# BiphasicBoardv2.net
KiCad netlist of a schematic drawn in EAGLE
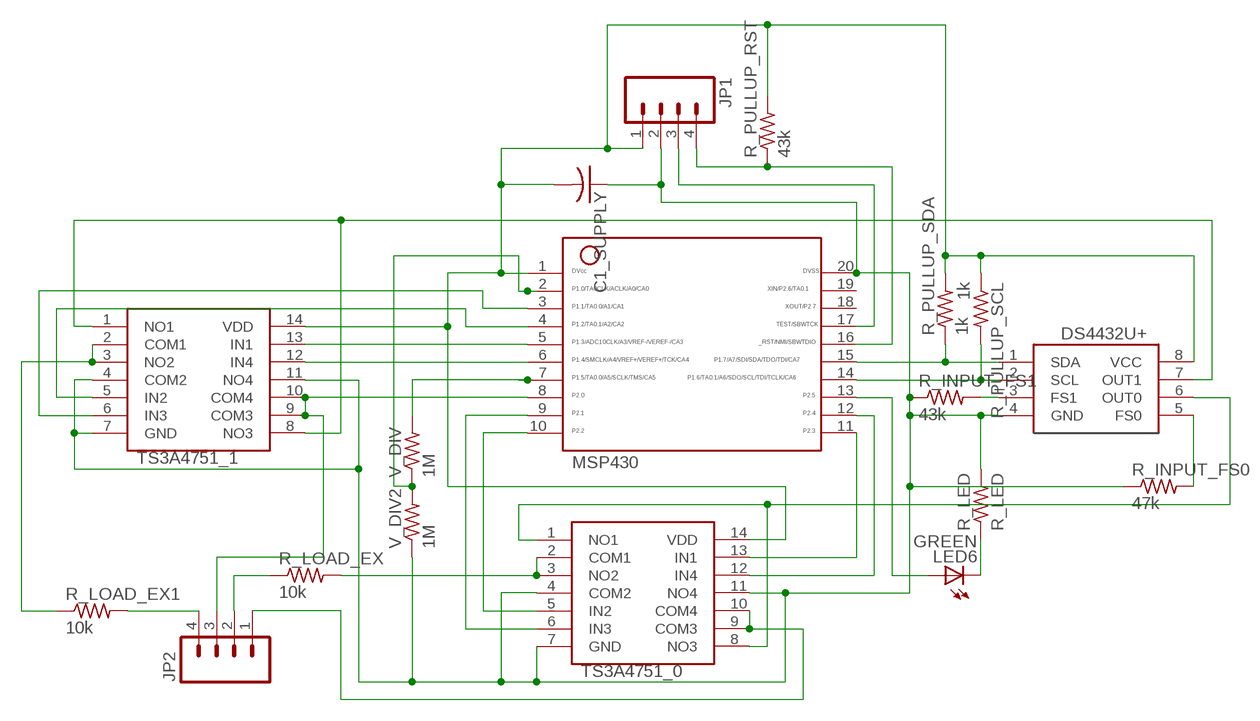
[diagram p0: schematic, sheet 1]

(export (version "E")
  (design (tool "Eeschema 10.0.6"))
  (components
    (comp (ref "C1_SUPPLY")
      (value "C-USC0603")
      (footprint "eagle-import:C0603")
      (libsource (lib "eagle-import") (part "C-USC0603"))
    )
    (comp (ref "DS4432U+")
      (value "DS4432U+")
      (footprint "eagle-import:8_PIN")
      (libsource (lib "eagle-import") (part "DS4432U+"))
    )
    (comp (ref "JP1")
      (value "M041.27MM")
      (footprint "eagle-import:1X04-1.27MM")
      (libsource (lib "eagle-import") (part "M041.27MM"))
    )
    (comp (ref "JP2")
      (value "M041.27MM")
      (footprint "eagle-import:1X04-1.27MM")
      (libsource (lib "eagle-import") (part "M041.27MM"))
    )
    (comp (ref "LED6")
      (value "GREEN")
      (footprint "eagle-import:LED-1206")
      (libsource (lib "eagle-import") (part "LED1206"))
    )
    (comp (ref "MSP430")
      (value "MSP430")
      (footprint "eagle-import:20_PIN")
      (libsource (lib "eagle-import") (part "MSP430"))
    )
    (comp (ref "R_INPUT_FS0")
      (value "47k")
      (footprint "eagle-import:R0603")
      (libsource (lib "eagle-import") (part "R-US_R0603"))
    )
    (comp (ref "R_INPUT_FS1")
      (value "43k")
      (footprint "eagle-import:R0603")
      (libsource (lib "eagle-import") (part "R-US_R0603"))
    )
    (comp (ref "R_LED")
      (value "R_LED")
      (footprint "eagle-import:R0603")
      (libsource (lib "eagle-import") (part "R-US_R0603"))
    )
    (comp (ref "R_LOAD_EX")
      (value "10k")
      (footprint "eagle-import:R0603")
      (libsource (lib "eagle-import") (part "R-US_R0603"))
    )
    (comp (ref "R_LOAD_EX1")
      (value "10k")
      (footprint "eagle-import:R0603")
      (libsource (lib "eagle-import") (part "R-US_R0603"))
    )
    (comp (ref "R_PULLUP_RST")
      (value "43k")
      (footprint "eagle-import:R0603")
      (libsource (lib "eagle-import") (part "R-US_R0603"))
    )
    (comp (ref "R_PULLUP_SCL")
      (value "1k")
      (footprint "eagle-import:R0603")
      (libsource (lib "eagle-import") (part "R-US_R0603"))
    )
    (comp (ref "R_PULLUP_SDA")
      (value "1k")
      (footprint "eagle-import:R0603")
      (libsource (lib "eagle-import") (part "R-US_R0603"))
    )
    (comp (ref "TS3A4751_0")
      (value "TS3A4751")
      (footprint "eagle-import:14_PIN")
      (libsource (lib "eagle-import") (part "TS3A4751"))
    )
    (comp (ref "TS3A4751_1")
      (value "TS3A4751")
      (footprint "eagle-import:14_PIN")
      (libsource (lib "eagle-import") (part "TS3A4751"))
    )
    (comp (ref "V_DIV")
      (value "1M")
      (footprint "eagle-import:R0603")
      (libsource (lib "eagle-import") (part "R-US_R0603"))
    )
    (comp (ref "V_DIV2")
      (value "1M")
      (footprint "eagle-import:R0603")
      (libsource (lib "eagle-import") (part "R-US_R0603"))
    )
  )
  (nets
    (net (code "1") (name "Net-(DS4432U+-FS0)") (class "Default")
      (node (ref "DS4432U+") (pin "5") (pinfunction "FS0_5") (pintype "bidirectional"))
      (node (ref "R_INPUT_FS0") (pin "2") (pinfunction "2_2") (pintype "passive"))
    )
    (net (code "2") (name "Net-(DS4432U+-FS1)") (class "Default")
      (node (ref "DS4432U+") (pin "3") (pinfunction "FS1_3") (pintype "bidirectional"))
      (node (ref "R_INPUT_FS1") (pin "2") (pinfunction "2_2") (pintype "passive"))
    )
    (net (code "3") (name "Net-(DS4432U+-GND)") (class "Default")
      (node (ref "C1_SUPPLY") (pin "1") (pinfunction "1_1") (pintype "passive"))
      (node (ref "DS4432U+") (pin "4") (pinfunction "GND_4") (pintype "bidirectional"))
      (node (ref "JP1") (pin "2") (pinfunction "2_2") (pintype "passive"))
      (node (ref "MSP430") (pin "20") (pinfunction "20_20") (pintype "bidirectional"))
      (node (ref "R_INPUT_FS0") (pin "1") (pinfunction "1_1") (pintype "passive"))
      (node (ref "R_INPUT_FS1") (pin "1") (pinfunction "1_1") (pintype "passive"))
      (node (ref "R_LED") (pin "2") (pinfunction "2_2") (pintype "passive"))
      (node (ref "TS3A4751_0") (pin "11") (pinfunction "NO4_11") (pintype "bidirectional"))
      (node (ref "TS3A4751_0") (pin "4") (pinfunction "COM2_4") (pintype "bidirectional"))
      (node (ref "TS3A4751_0") (pin "7") (pinfunction "GND_7") (pintype "bidirectional"))
      (node (ref "TS3A4751_1") (pin "11") (pinfunction "NO4_11") (pintype "bidirectional"))
      (node (ref "TS3A4751_1") (pin "4") (pinfunction "COM2_4") (pintype "bidirectional"))
      (node (ref "TS3A4751_1") (pin "7") (pinfunction "GND_7") (pintype "bidirectional"))
      (node (ref "V_DIV2") (pin "1") (pinfunction "1_1") (pintype "passive"))
    )
    (net (code "4") (name "Net-(DS4432U+-OUT0)") (class "Default")
      (node (ref "DS4432U+") (pin "6") (pinfunction "OUT0_6") (pintype "bidirectional"))
      (node (ref "TS3A4751_0") (pin "1") (pinfunction "NO1_1") (pintype "bidirectional"))
      (node (ref "TS3A4751_0") (pin "8") (pinfunction "NO3_8") (pintype "bidirectional"))
    )
    (net (code "5") (name "Net-(DS4432U+-OUT1)") (class "Default")
      (node (ref "DS4432U+") (pin "7") (pinfunction "OUT1_7") (pintype "bidirectional"))
      (node (ref "TS3A4751_1") (pin "1") (pinfunction "NO1_1") (pintype "bidirectional"))
      (node (ref "TS3A4751_1") (pin "8") (pinfunction "NO3_8") (pintype "bidirectional"))
    )
    (net (code "6") (name "Net-(DS4432U+-SCL)") (class "Default")
      (node (ref "DS4432U+") (pin "2") (pinfunction "SCL_2") (pintype "bidirectional"))
      (node (ref "MSP430") (pin "14") (pinfunction "14_14") (pintype "bidirectional"))
      (node (ref "R_PULLUP_SCL") (pin "2") (pinfunction "2_2") (pintype "passive"))
    )
    (net (code "7") (name "Net-(DS4432U+-SDA)") (class "Default")
      (node (ref "DS4432U+") (pin "1") (pinfunction "SDA_1") (pintype "bidirectional"))
      (node (ref "MSP430") (pin "15") (pinfunction "15_15") (pintype "bidirectional"))
      (node (ref "R_PULLUP_SDA") (pin "1") (pinfunction "1_1") (pintype "passive"))
    )
    (net (code "8") (name "Net-(DS4432U+-VCC)") (class "Default")
      (node (ref "C1_SUPPLY") (pin "2") (pinfunction "2_2") (pintype "passive"))
      (node (ref "DS4432U+") (pin "8") (pinfunction "VCC_8") (pintype "bidirectional"))
      (node (ref "JP1") (pin "1") (pinfunction "1_1") (pintype "passive"))
      (node (ref "MSP430") (pin "1") (pinfunction "1_1") (pintype "bidirectional"))
      (node (ref "R_PULLUP_RST") (pin "2") (pinfunction "2_2") (pintype "passive"))
      (node (ref "R_PULLUP_SCL") (pin "1") (pinfunction "1_1") (pintype "passive"))
      (node (ref "R_PULLUP_SDA") (pin "2") (pinfunction "2_2") (pintype "passive"))
      (node (ref "TS3A4751_0") (pin "14") (pinfunction "VDD_14") (pintype "bidirectional"))
      (node (ref "TS3A4751_1") (pin "14") (pinfunction "VDD_14") (pintype "bidirectional"))
    )
    (net (code "9") (name "Net-(JP1-Pad3)") (class "Default")
      (node (ref "JP1") (pin "3") (pinfunction "3_3") (pintype "passive"))
      (node (ref "MSP430") (pin "17") (pinfunction "17_17") (pintype "bidirectional"))
    )
    (net (code "10") (name "Net-(JP1-Pad4)") (class "Default")
      (node (ref "JP1") (pin "4") (pinfunction "4_4") (pintype "passive"))
      (node (ref "MSP430") (pin "16") (pinfunction "16_16") (pintype "bidirectional"))
      (node (ref "R_PULLUP_RST") (pin "1") (pinfunction "1_1") (pintype "passive"))
    )
    (net (code "11") (name "Net-(JP2-Pad2)") (class "Default")
      (node (ref "JP2") (pin "2") (pinfunction "2_2") (pintype "passive"))
      (node (ref "R_LOAD_EX") (pin "1") (pinfunction "1_1") (pintype "passive"))
    )
    (net (code "12") (name "Net-(JP2-Pad4)") (class "Default")
      (node (ref "JP2") (pin "4") (pinfunction "4_4") (pintype "passive"))
      (node (ref "R_LOAD_EX1") (pin "2") (pinfunction "2_2") (pintype "passive"))
    )
    (net (code "13") (name "Net-(LED6-PadA)") (class "Default")
      (node (ref "LED6") (pin "A") (pinfunction "A_A") (pintype "passive"))
      (node (ref "MSP430") (pin "13") (pinfunction "13_13") (pintype "bidirectional"))
    )
    (net (code "14") (name "Net-(LED6-PadC)") (class "Default")
      (node (ref "LED6") (pin "C") (pinfunction "C_C") (pintype "passive"))
      (node (ref "R_LED") (pin "1") (pinfunction "1_1") (pintype "passive"))
    )
    (net (code "15") (name "Net-(MSP430-Pad2)") (class "Default")
      (node (ref "MSP430") (pin "2") (pinfunction "2_2") (pintype "bidirectional"))
      (node (ref "V_DIV") (pin "1") (pinfunction "1_1") (pintype "passive"))
      (node (ref "V_DIV2") (pin "2") (pinfunction "2_2") (pintype "passive"))
    )
    (net (code "16") (name "Net-(MSP430-Pad7)") (class "Default")
      (node (ref "MSP430") (pin "7") (pinfunction "7_7") (pintype "bidirectional"))
      (node (ref "V_DIV") (pin "2") (pinfunction "2_2") (pintype "passive"))
    )
    (net (code "17") (name "Net-(TS3A4751_0-COM1)") (class "Default")
      (node (ref "R_LOAD_EX") (pin "2") (pinfunction "2_2") (pintype "passive"))
      (node (ref "TS3A4751_0") (pin "2") (pinfunction "COM1_2") (pintype "bidirectional"))
      (node (ref "TS3A4751_0") (pin "3") (pinfunction "NO2_3") (pintype "bidirectional"))
    )
    (net (code "18") (name "Net-(TS3A4751_0-COM3)") (class "Default")
      (node (ref "JP2") (pin "1") (pinfunction "1_1") (pintype "passive"))
      (node (ref "TS3A4751_0") (pin "10") (pinfunction "COM4_10") (pintype "bidirectional"))
      (node (ref "TS3A4751_0") (pin "9") (pinfunction "COM3_9") (pintype "bidirectional"))
    )
    (net (code "19") (name "Net-(TS3A4751_0-IN1)") (class "Default")
      (node (ref "MSP430") (pin "11") (pinfunction "11_11") (pintype "bidirectional"))
      (node (ref "TS3A4751_0") (pin "13") (pinfunction "IN1_13") (pintype "bidirectional"))
    )
    (net (code "20") (name "Net-(TS3A4751_0-IN2)") (class "Default")
      (node (ref "MSP430") (pin "10") (pinfunction "10_10") (pintype "bidirectional"))
      (node (ref "TS3A4751_0") (pin "5") (pinfunction "IN2_5") (pintype "bidirectional"))
    )
    (net (code "21") (name "Net-(TS3A4751_0-IN3)") (class "Default")
      (node (ref "MSP430") (pin "9") (pinfunction "9_9") (pintype "bidirectional"))
      (node (ref "TS3A4751_0") (pin "6") (pinfunction "IN3_6") (pintype "bidirectional"))
    )
    (net (code "22") (name "Net-(TS3A4751_0-IN4)") (class "Default")
      (node (ref "MSP430") (pin "12") (pinfunction "12_12") (pintype "bidirectional"))
      (node (ref "TS3A4751_0") (pin "12") (pinfunction "IN4_12") (pintype "bidirectional"))
    )
    (net (code "23") (name "Net-(TS3A4751_1-COM1)") (class "Default")
      (node (ref "R_LOAD_EX1") (pin "1") (pinfunction "1_1") (pintype "passive"))
      (node (ref "TS3A4751_1") (pin "2") (pinfunction "COM1_2") (pintype "bidirectional"))
      (node (ref "TS3A4751_1") (pin "3") (pinfunction "NO2_3") (pintype "bidirectional"))
    )
    (net (code "24") (name "Net-(TS3A4751_1-COM3)") (class "Default")
      (node (ref "JP2") (pin "3") (pinfunction "3_3") (pintype "passive"))
      (node (ref "MSP430") (pin "8") (pinfunction "8_8") (pintype "bidirectional"))
      (node (ref "TS3A4751_1") (pin "10") (pinfunction "COM4_10") (pintype "bidirectional"))
      (node (ref "TS3A4751_1") (pin "9") (pinfunction "COM3_9") (pintype "bidirectional"))
    )
    (net (code "25") (name "Net-(TS3A4751_1-IN1)") (class "Default")
      (node (ref "MSP430") (pin "5") (pinfunction "5_5") (pintype "bidirectional"))
      (node (ref "TS3A4751_1") (pin "13") (pinfunction "IN1_13") (pintype "bidirectional"))
    )
    (net (code "26") (name "Net-(TS3A4751_1-IN2)") (class "Default")
      (node (ref "MSP430") (pin "4") (pinfunction "4_4") (pintype "bidirectional"))
      (node (ref "TS3A4751_1") (pin "5") (pinfunction "IN2_5") (pintype "bidirectional"))
    )
    (net (code "27") (name "Net-(TS3A4751_1-IN3)") (class "Default")
      (node (ref "MSP430") (pin "3") (pinfunction "3_3") (pintype "bidirectional"))
      (node (ref "TS3A4751_1") (pin "6") (pinfunction "IN3_6") (pintype "bidirectional"))
    )
    (net (code "28") (name "Net-(TS3A4751_1-IN4)") (class "Default")
      (node (ref "MSP430") (pin "6") (pinfunction "6_6") (pintype "bidirectional"))
      (node (ref "TS3A4751_1") (pin "12") (pinfunction "IN4_12") (pintype "bidirectional"))
    )
    (net (code "29") (name "unconnected-(MSP430-Pad18)") (class "Default")
      (node (ref "MSP430") (pin "18") (pinfunction "18_18") (pintype "bidirectional"))
    )
    (net (code "30") (name "unconnected-(MSP430-Pad19)") (class "Default")
      (node (ref "MSP430") (pin "19") (pinfunction "19_19") (pintype "bidirectional"))
    )
  )
)
